# RS485_Com_and_Connectors.net
KiCad netlist of a schematic drawn in Altium Designer
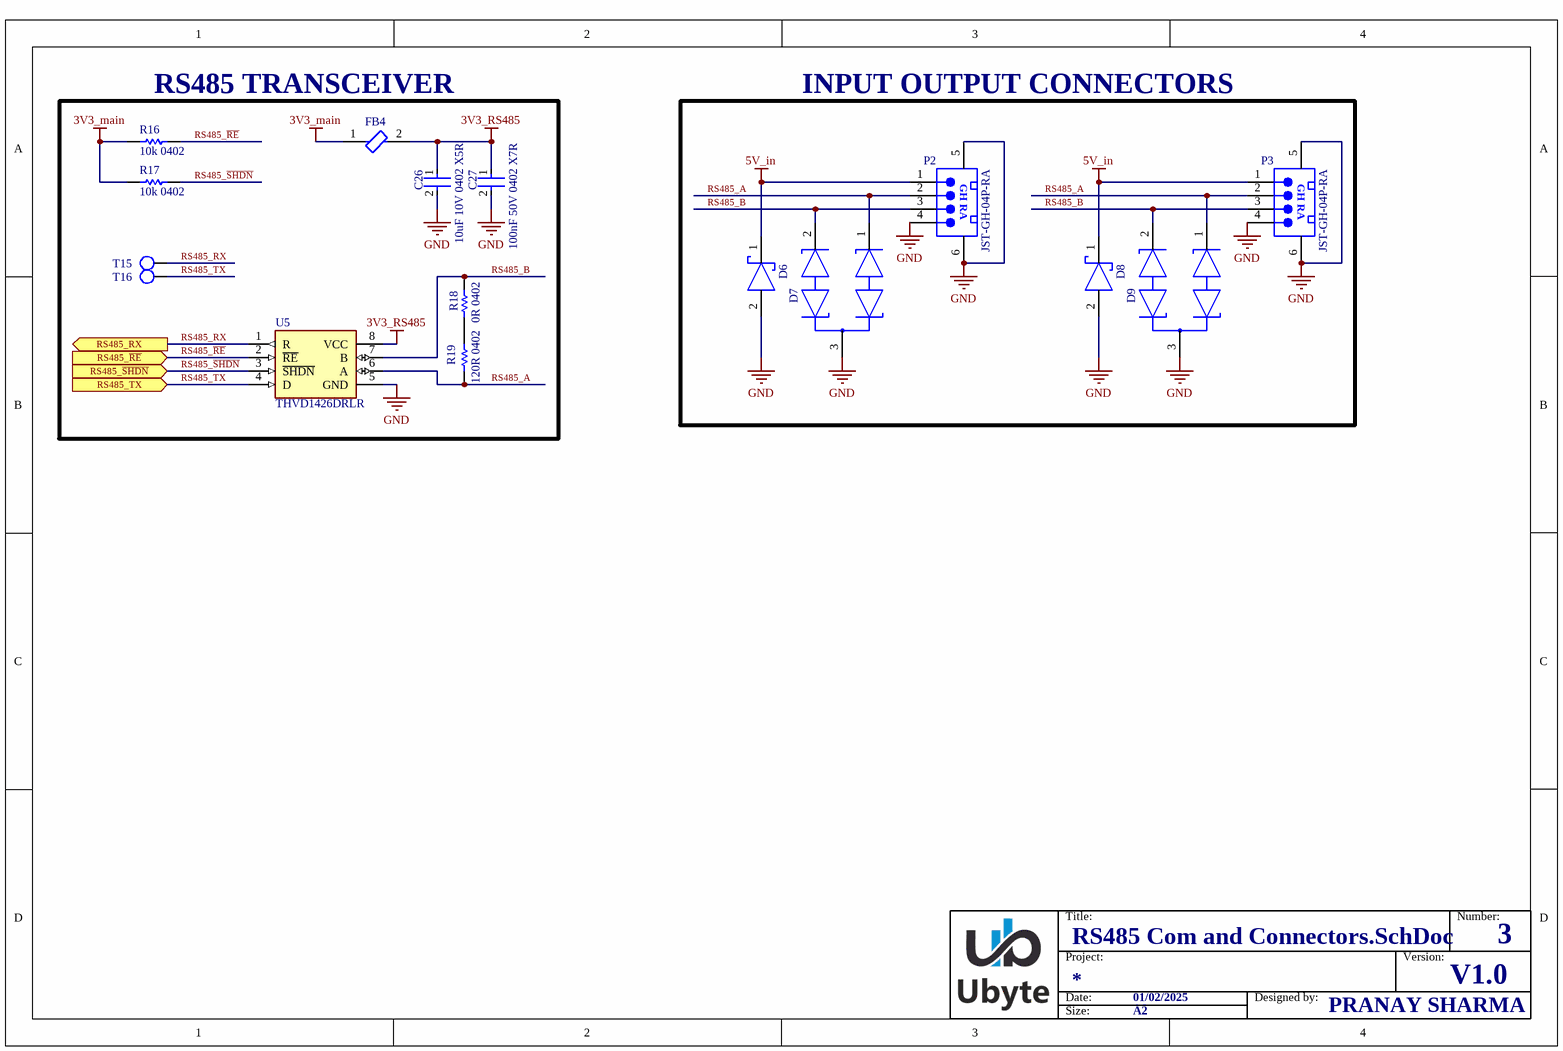
[diagram p0: RS485 Com and Connectors.SchDoc]

(export (version "E")
  (design (tool "Eeschema 10.0.6"))
  (components
    (comp (ref "C26")
      (value "10uF 10V 0402 X5R")
      (footprint "Res, Cap, Ind, LED, FB_Lib:0402 IPC CLASS C CAPACITOR")
      (libsource (lib "Capacitor_Lib") (part "10uF 10V 0402 X5R"))
    )
    (comp (ref "C27")
      (value "100nF 50V 0402 X7R")
      (footprint "Res, Cap, Ind, LED, FB_Lib:0402 IPC CLASS C CAPACITOR")
      (libsource (lib "Capacitor_Lib") (part "100nF 50V 0402 X7R"))
    )
    (comp (ref "D6")
      (value "SP3031-01ETG")
      (footprint "Res, Cap, Ind, LED, FB_Lib:SOD882 IPC-C")
      (libsource (lib "Diodes_Lib") (part "SP3031-01ETG"))
    )
    (comp (ref "D7")
      (value "SM712")
      (footprint "Res, Cap, Ind, LED, FB_Lib:FP-SOT23-IPC_C")
      (libsource (lib "Diodes_Lib") (part "SM712"))
    )
    (comp (ref "D8")
      (value "SP3031-01ETG")
      (footprint "Res, Cap, Ind, LED, FB_Lib:SOD882 IPC-C")
      (libsource (lib "Diodes_Lib") (part "SP3031-01ETG"))
    )
    (comp (ref "D9")
      (value "SM712")
      (footprint "Res, Cap, Ind, LED, FB_Lib:FP-SOT23-IPC_C")
      (libsource (lib "Diodes_Lib") (part "SM712"))
    )
    (comp (ref "FB4")
      (value "BLM15AX102SN1D")
      (footprint "Res, Cap, Ind, LED, FB_Lib:0402 IPC CLASS C FERRITE BEAD")
      (libsource (lib "Ferrite_Bead_Lib") (part "BLM15AX102SN1D"))
    )
    (comp (ref "P2")
      (value "JST-GH-04P-RA")
      (footprint "Connectors_Lib:JST-GH-04P-RA")
      (libsource (lib "Connectors_Lib") (part "JST-GH-04P-RA"))
    )
    (comp (ref "P3")
      (value "JST-GH-04P-RA")
      (footprint "Connectors_Lib:JST-GH-04P-RA")
      (libsource (lib "Connectors_Lib") (part "JST-GH-04P-RA"))
    )
    (comp (ref "R16")
      (value "10k 0402")
      (footprint "Res, Cap, Ind, LED, FB_Lib:0402 IPC CLASS C RESISTOR")
      (libsource (lib "Resistor_Lib") (part "10k 1% 0402"))
    )
    (comp (ref "R17")
      (value "10k 0402")
      (footprint "Res, Cap, Ind, LED, FB_Lib:0402 IPC CLASS C RESISTOR")
      (libsource (lib "Resistor_Lib") (part "10k 1% 0402"))
    )
    (comp (ref "R18")
      (value "0R 0402")
      (footprint "Res, Cap, Ind, LED, FB_Lib:0402 IPC CLASS B RESISTOR")
      (libsource (lib "Resistor_Lib") (part "0R 1% 0402"))
    )
    (comp (ref "R19")
      (value "120R 0402")
      (footprint "Res, Cap, Ind, LED, FB_Lib:0402 IPC CLASS C RESISTOR")
      (libsource (lib "Resistor_Lib") (part "120R 1% 0402"))
    )
    (comp (ref "T15")
      (value "TP")
      (footprint "Miscellaneous_Lib:Testpoint1")
      (libsource (lib "Miscellaneous_Lib") (part "Testpoint1"))
    )
    (comp (ref "T16")
      (value "TP")
      (footprint "Miscellaneous_Lib:Testpoint1")
      (libsource (lib "Miscellaneous_Lib") (part "Testpoint1"))
    )
    (comp (ref "U5")
      (value "THVD1426DRLR")
      (footprint "Integrated_Circuits_Lib:DRL0008A IPC-C")
      (libsource (lib "Integrated_Circuits_Lib") (part "THVD1426DRLR"))
    )
  )
  (nets
    (net (code "1") (name "/RS485_A") (class "Default")
      (node (ref "D7") (pin "1") (pinfunction "K1_1") (pintype "passive"))
      (node (ref "D9") (pin "1") (pinfunction "K1_1") (pintype "passive"))
      (node (ref "P2") (pin "2") (pinfunction "2_2") (pintype "passive"))
      (node (ref "P3") (pin "2") (pinfunction "2_2") (pintype "passive"))
      (node (ref "R19") (pin "1") (pinfunction "1_1") (pintype "passive"))
      (node (ref "U5") (pin "6") (pinfunction "A_6") (pintype "bidirectional"))
    )
    (net (code "2") (name "/RS485_B") (class "Default")
      (node (ref "D7") (pin "2") (pinfunction "K2_2") (pintype "passive"))
      (node (ref "D9") (pin "2") (pinfunction "K2_2") (pintype "passive"))
      (node (ref "P2") (pin "3") (pinfunction "3_3") (pintype "passive"))
      (node (ref "P3") (pin "3") (pinfunction "3_3") (pintype "passive"))
      (node (ref "R18") (pin "2") (pinfunction "2_2") (pintype "passive"))
      (node (ref "U5") (pin "7") (pinfunction "B_7") (pintype "bidirectional"))
    )
    (net (code "3") (name "/RS485_RX") (class "Default")
      (node (ref "T15") (pin "0") (pinfunction "0_0") (pintype "passive"))
      (node (ref "U5") (pin "1") (pinfunction "R_1") (pintype "output"))
    )
    (net (code "4") (name "/RS485_TX") (class "Default")
      (node (ref "T16") (pin "0") (pinfunction "0_0") (pintype "passive"))
      (node (ref "U5") (pin "4") (pinfunction "D_4") (pintype "input"))
    )
    (net (code "5") (name "/RS485_~{RE}") (class "Default")
      (node (ref "R16") (pin "1") (pinfunction "1_1") (pintype "passive"))
      (node (ref "U5") (pin "2") (pinfunction "~{RE}_2") (pintype "input"))
    )
    (net (code "6") (name "/RS485_~{SHDN}") (class "Default")
      (node (ref "R17") (pin "1") (pinfunction "1_1") (pintype "passive"))
      (node (ref "U5") (pin "3") (pinfunction "~{SHDN}_3") (pintype "input"))
    )
    (net (code "7") (name "3V3_RS485") (class "Default")
      (node (ref "C26") (pin "1") (pinfunction "1_1") (pintype "passive"))
      (node (ref "C27") (pin "1") (pinfunction "1_1") (pintype "passive"))
      (node (ref "FB4") (pin "2") (pinfunction "2_2") (pintype "passive"))
      (node (ref "U5") (pin "8") (pinfunction "VCC_8") (pintype "power_in"))
    )
    (net (code "8") (name "3V3_main") (class "Default")
      (node (ref "FB4") (pin "1") (pinfunction "1_1") (pintype "passive"))
      (node (ref "R16") (pin "2") (pinfunction "2_2") (pintype "passive"))
      (node (ref "R17") (pin "2") (pinfunction "2_2") (pintype "passive"))
    )
    (net (code "9") (name "5V_in") (class "Default")
      (node (ref "D6") (pin "1") (pinfunction "C_1") (pintype "passive"))
      (node (ref "D8") (pin "1") (pinfunction "C_1") (pintype "passive"))
      (node (ref "P2") (pin "1") (pinfunction "1_1") (pintype "passive"))
      (node (ref "P3") (pin "1") (pinfunction "1_1") (pintype "passive"))
    )
    (net (code "10") (name "GND") (class "Default")
      (node (ref "C26") (pin "2") (pinfunction "2_2") (pintype "passive"))
      (node (ref "C27") (pin "2") (pinfunction "2_2") (pintype "passive"))
      (node (ref "D6") (pin "2") (pinfunction "A_2") (pintype "passive"))
      (node (ref "D7") (pin "3") (pinfunction "CC_3") (pintype "passive"))
      (node (ref "D8") (pin "2") (pinfunction "A_2") (pintype "passive"))
      (node (ref "D9") (pin "3") (pinfunction "CC_3") (pintype "passive"))
      (node (ref "P2") (pin "4") (pinfunction "4_4") (pintype "passive"))
      (node (ref "P2") (pin "5") (pinfunction "5_5") (pintype "passive"))
      (node (ref "P2") (pin "6") (pinfunction "6_6") (pintype "passive"))
      (node (ref "P3") (pin "4") (pinfunction "4_4") (pintype "passive"))
      (node (ref "P3") (pin "5") (pinfunction "5_5") (pintype "passive"))
      (node (ref "P3") (pin "6") (pinfunction "6_6") (pintype "passive"))
      (node (ref "U5") (pin "5") (pinfunction "GND_5") (pintype "power_in"))
    )
    (net (code "11") (name "Net-(R18-Pad1)") (class "Default")
      (node (ref "R18") (pin "1") (pinfunction "1_1") (pintype "passive"))
      (node (ref "R19") (pin "2") (pinfunction "2_2") (pintype "passive"))
    )
  )
)
